# AFE_Channel_4.net
KiCad netlist of a schematic drawn in Altium Designer
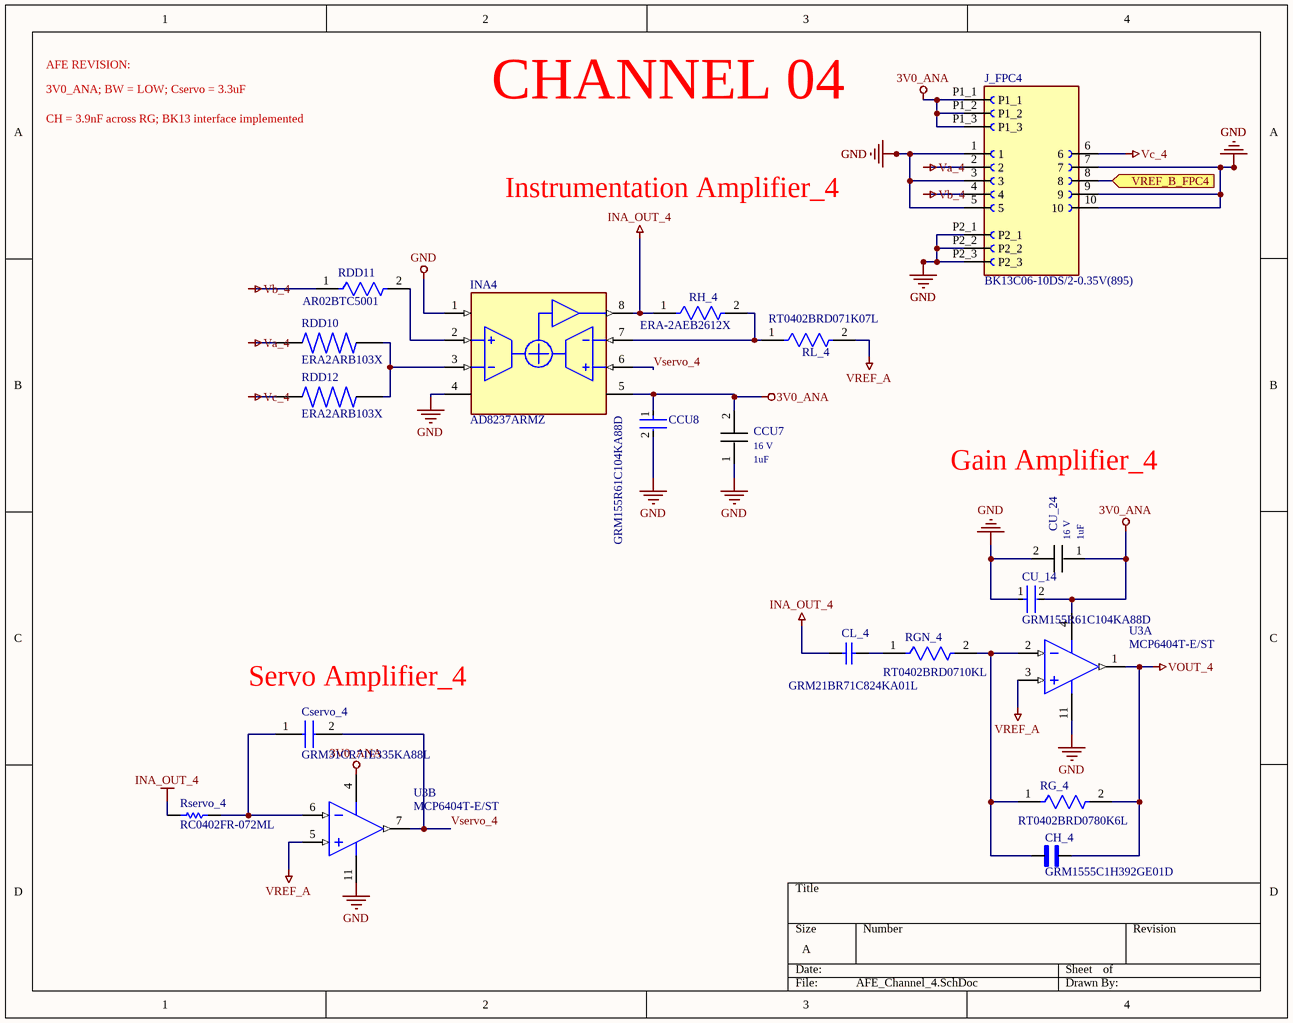
[diagram p0: AFE_Channel_4.SchDoc]

(export (version "E")
  (design (tool "Eeschema 10.0.6"))
  (components
    (comp (ref "CCU7")
      (value "MURATA_GRM155C71C105KE11D")
      (footprint "MURATA_GRM155C71C105KE11D_0:*MURATA_GRM155C71C105KE11D_0")
      (description "Murata GRM155C71C105KE11D: 1 uF 16 V X7S +/-10%, 0402/1005 metric")
      (fields (field (name "MF") "Murata") (field (name "MP") "GRM155C71C105KE11D"))
      (libsource (lib "EMG_Controlled_R5") (part "EMG_R5_CCU7"))
    )
    (comp (ref "CCU8")
      (value "GRM155R61C104KA88D")
      (footprint "96DF66F8-B997-472F-A885-42BCAAE661B2_FP-GRM155-0_05-IPC_C:FP-GRM155-0_05-IPC_C")
      (description "CAP CER 0.1UF 16V X5R 0402")
      (fields (field (name "VOLTAGE") "16V") (field (name "TOLERANCE") "10%"))
      (libsource (lib "EMG_Controlled_R5") (part "EMG_R5_CCU8"))
    )
    (comp (ref "CH_4")
      (value "GRM1555C1H392GE01D")
      (footprint "GRM1555C1H392GE01D_0:CAPC1005X55N")
      (description "SMD capacitor C0G(EIA) with capacitance 3900pF Tol.2%. Rated voltage 50Vdc 125C")
      (fields (field (name "MF") "Murata Electronics"))
      (libsource (lib "EMG_Controlled_R5") (part "EMG_R5_CH_4"))
    )
    (comp (ref "CL_4")
      (value "GRM21BR71C824KA01L")
      (footprint "987105EF-01FA-4198-A59F-44D3B68BB40E_CAPC2013X135X45ML10T25:CAPC2013X135X45ML10T25")
      (fields (field (name "MANUFACTURER") "Murata"))
      (libsource (lib "EMG_Controlled_R5") (part "EMG_R5_CL_4"))
    )
    (comp (ref "Cservo_4")
      (value "GRM31CR71E335KA88L")
      (footprint "SamacSys:GRM31x")
      (description "Capacitor")
      (fields
        (field (name "MOUSER PART NUMBER") "81-GRM31CR71E335KA8L")
        (field (name "MANUFACTURER") "Murata")
      )
      (libsource (lib "EMG_Controlled_R5") (part "EMG_R5_Cservo_4"))
    )
    (comp (ref "CU_14")
      (value "GRM155R61C104KA88D")
      (footprint "96DF66F8-B997-472F-A885-42BCAAE661B2_FP-GRM155-0_05-IPC_C:FP-GRM155-0_05-IPC_C")
      (description "CAP CER 0.1UF 16V X5R 0402")
      (fields (field (name "VOLTAGE") "16V") (field (name "TOLERANCE") "10%"))
      (libsource (lib "EMG_Controlled_R5") (part "EMG_R5_CU_14"))
    )
    (comp (ref "CU_24")
      (value "MURATA_GRM155C71C105KE11D")
      (footprint "MURATA_GRM155C71C105KE11D_0:*MURATA_GRM155C71C105KE11D_0")
      (description "Murata GRM155C71C105KE11D: 1 uF 16 V X7S +/-10%, 0402/1005 metric")
      (fields (field (name "MF") "Murata") (field (name "MP") "GRM155C71C105KE11D"))
      (libsource (lib "EMG_Controlled_R5") (part "EMG_R5_CU_24"))
    )
    (comp (ref "INA4")
      (value "AD8237ARMZ")
      (footprint "EMG_AD8237_R3:EMG_AD8237_R3_MSOP8")
      (description "Micropower, Zero Drift, True Rail-to-Rail Instrumentation Amplifier")
      (fields (field (name "MF") "Analog Devices"))
      (libsource (lib "EMG_Controlled_R5") (part "EMG_R5_INA4"))
    )
    (comp (ref "J_FPC4")
      (value "BK13C06-10DS/2-0.35V(895)")
      (footprint "BK13C06-10DS_2-0.35V_895__0:HIROSE_BK13C06-10DS/2-0.35V(895)")
      (description "10 Position Connector Receptacle, Center Strip Contacts Surface Mount Gold")
      (fields (field (name "MF") "Hirose Electric Co Ltd"))
      (libsource (lib "EMG_Controlled_R5") (part "EMG_R5_J_FPC4"))
    )
    (comp (ref "RDD10")
      (value "ERA2ARB103X")
      (footprint "ERA2ARB103X_0:RES_ERA2ARB103X")
      (libsource (lib "EMG_Controlled_R5") (part "EMG_R5_RDD10"))
    )
    (comp (ref "RDD11")
      (value "AR02BTC5001")
      (footprint "7D606042-220B-45EE-95DD-CA1A974E4C0D_FP-AC0402-MFG:FP-AC0402-MFG")
      (description "-55℃~+155℃ 50V 5kΩ 63mW Thin Film Resistor ±0.1% ±25ppm/℃ 0402 Chip Resistor - Surface Mount ROH")
      (fields
        (field (name "MANUFACTURER") "Viking Tech")
        (field (name "OCTOPART") "https://octopart.com/datasheet/viking-tech/AR02BTC5001")
      )
      (libsource (lib "EMG_Controlled_R5") (part "EMG_R5_RDD11"))
    )
    (comp (ref "RDD12")
      (value "ERA2ARB103X")
      (footprint "ERA2ARB103X_0:RES_ERA2ARB103X")
      (libsource (lib "EMG_Controlled_R5") (part "EMG_R5_RDD12"))
    )
    (comp (ref "RGN_4")
      (value "RT0402BRD0710KL")
      (footprint "B876F212-A29A-4983-9BB8-539D1BA2EBA1_FP-RT0402-MFG:FP-RT0402-MFG")
      (description "RES 10.0K OHM 1/16W .1% SMD 0402")
      (fields
        (field (name "MANUFACTURER") "Yageo")
        (field (name "OCTOPART") "https://octopart.com/rt0402brd0710kl-yageo-1181432")
      )
      (libsource (lib "EMG_Controlled_R5") (part "EMG_R5_RGN_4"))
    )
    (comp (ref "RG_4")
      (value "RT0402BRD0780K6L")
      (footprint "B876F212-A29A-4983-9BB8-539D1BA2EBA1_FP-RT0402-MFG:FP-RT0402-MFG")
      (description "RES SMD 80.6KOHM 0.1% 1/16W 0402")
      (fields
        (field (name "MANUFACTURER") "Yageo")
        (field (name "OCTOPART") "https://octopart.com/rt0402brd0780k6l-yageo-1468076")
      )
      (libsource (lib "EMG_Controlled_R5") (part "EMG_R5_RG_4"))
    )
    (comp (ref "RH_4")
      (value "ERA-2AEB2612X")
      (footprint "1CBBEC27-AD79-48E8-A701-2E235EA9F8F2_FP-AC0402-IPC_A:FP-AC0402-IPC_A")
      (description "RES 26.1kΩ ±0.1% 0.063W 0402")
      (fields (field (name "TOLERANCE") "0.1%") (field (name "MANUFACTURER") "PANASONIC"))
      (libsource (lib "EMG_Controlled_R5") (part "EMG_R5_RH_4"))
    )
    (comp (ref "RL_4")
      (value "RT0402BRD071K07L")
      (footprint "B876F212-A29A-4983-9BB8-539D1BA2EBA1_FP-RT0402-MFG:FP-RT0402-MFG")
      (description "RES SMD 1.07K OHM 0.1% 1/16W")
      (fields
        (field (name "OCTOPART") "https://octopart.com/rt0402brd071k07l-yageo-1400807")
        (field (name "MANUFACTURER") "Yageo")
      )
      (libsource (lib "EMG_Controlled_R5") (part "EMG_R5_RL_4"))
    )
    (comp (ref "Rservo_4")
      (value "RC0402FR-072ML")
      (footprint "3EB15388-1759-44FF-BAE1-1F0823F3E8F1_RESC1005X40X25NL05T10:RESC1005X40X25NL05T10")
      (fields (field (name "MANUFACTURER") "Yageo / Phycomp"))
      (libsource (lib "EMG_Controlled_R5") (part "EMG_R5_Rservo_4"))
    )
    (comp (ref "U3")
      (value "MCP6404T-E/ST")
      (footprint "CEF93338-31F0-4C64-85B6-F650E0BB75E3_TSSOP-ST14_N:TSSOP-ST14_N")
      (description "None")
      (libsource (lib "EMG_Controlled_R5") (part "EMG_R5_U3"))
    )
  )
  (nets
    (net (code "1") (name "/VREF_B_FPC4") (class "Default")
      (node (ref "J_FPC4") (pin "8") (pinfunction "8_8") (pintype "passive"))
    )
    (net (code "2") (name "/Vservo_4") (class "Default")
      (node (ref "Cservo_4") (pin "2") (pinfunction "2_2") (pintype "passive"))
      (node (ref "INA4") (pin "6") (pinfunction "REF_6") (pintype "input"))
      (node (ref "U3") (pin "7") (pinfunction "VOUTB_7") (pintype "output"))
    )
    (net (code "3") (name "3V0_ANA") (class "Default")
      (node (ref "CCU7") (pin "2") (pinfunction "2_2") (pintype "passive"))
      (node (ref "CCU8") (pin "1") (pinfunction "1_1") (pintype "passive"))
      (node (ref "CU_14") (pin "2") (pinfunction "2_2") (pintype "passive"))
      (node (ref "CU_24") (pin "1") (pinfunction "1_1") (pintype "passive"))
      (node (ref "INA4") (pin "5") (pinfunction "+VS_5") (pintype "power_in"))
      (node (ref "J_FPC4") (pin "P1_1") (pinfunction "P1_1_P1_1") (pintype "power_in"))
      (node (ref "J_FPC4") (pin "P1_2") (pinfunction "P1_2_P1_2") (pintype "power_in"))
      (node (ref "J_FPC4") (pin "P1_3") (pinfunction "P1_3_P1_3") (pintype "power_in"))
      (node (ref "U3") (pin "4") (pinfunction "VDD_4") (pintype "power_in"))
    )
    (net (code "4") (name "GND") (class "Default")
      (node (ref "CCU7") (pin "1") (pinfunction "1_1") (pintype "passive"))
      (node (ref "CCU8") (pin "2") (pinfunction "2_2") (pintype "passive"))
      (node (ref "CU_14") (pin "1") (pinfunction "1_1") (pintype "passive"))
      (node (ref "CU_24") (pin "2") (pinfunction "2_2") (pintype "passive"))
      (node (ref "INA4") (pin "1") (pinfunction "BW_1") (pintype "input"))
      (node (ref "INA4") (pin "4") (pinfunction "-VS_4") (pintype "power_in"))
      (node (ref "J_FPC4") (pin "1") (pinfunction "1_1") (pintype "passive"))
      (node (ref "J_FPC4") (pin "10") (pinfunction "10_10") (pintype "passive"))
      (node (ref "J_FPC4") (pin "3") (pinfunction "3_3") (pintype "passive"))
      (node (ref "J_FPC4") (pin "5") (pinfunction "5_5") (pintype "passive"))
      (node (ref "J_FPC4") (pin "7") (pinfunction "7_7") (pintype "passive"))
      (node (ref "J_FPC4") (pin "9") (pinfunction "9_9") (pintype "passive"))
      (node (ref "J_FPC4") (pin "P2_1") (pinfunction "P2_1_P2_1") (pintype "power_in"))
      (node (ref "J_FPC4") (pin "P2_2") (pinfunction "P2_2_P2_2") (pintype "power_in"))
      (node (ref "J_FPC4") (pin "P2_3") (pinfunction "P2_3_P2_3") (pintype "power_in"))
      (node (ref "U3") (pin "11") (pinfunction "VSS_11") (pintype "power_in"))
    )
    (net (code "5") (name "INA_OUT_4") (class "Default")
      (node (ref "CL_4") (pin "2") (pinfunction "2_2") (pintype "passive"))
      (node (ref "INA4") (pin "8") (pinfunction "VOUT_8") (pintype "output"))
      (node (ref "RH_4") (pin "1") (pinfunction "1_1") (pintype "passive"))
      (node (ref "Rservo_4") (pin "2") (pinfunction "2_2") (pintype "passive"))
    )
    (net (code "6") (name "Net-(CL_4-Pad1)") (class "Default")
      (node (ref "CL_4") (pin "1") (pinfunction "1_1") (pintype "passive"))
      (node (ref "RGN_4") (pin "1") (pinfunction "1_1") (pintype "passive"))
    )
    (net (code "7") (name "Net-(INA4-+IN)") (class "Default")
      (node (ref "INA4") (pin "2") (pinfunction "+IN_2") (pintype "input"))
      (node (ref "RDD11") (pin "2") (pinfunction "2_2") (pintype "passive"))
    )
    (net (code "8") (name "Net-(INA4--IN)") (class "Default")
      (node (ref "INA4") (pin "3") (pinfunction "-IN_3") (pintype "input"))
      (node (ref "RDD10") (pin "2") (pinfunction "2_2") (pintype "passive"))
      (node (ref "RDD12") (pin "2") (pinfunction "2_2") (pintype "passive"))
    )
    (net (code "9") (name "Net-(INA4-FB)") (class "Default")
      (node (ref "INA4") (pin "7") (pinfunction "FB_7") (pintype "input"))
      (node (ref "RH_4") (pin "2") (pinfunction "2_2") (pintype "passive"))
      (node (ref "RL_4") (pin "1") (pinfunction "1_1") (pintype "passive"))
    )
    (net (code "10") (name "Net-(U3A-VINA-)") (class "Default")
      (node (ref "CH_4") (pin "2") (pinfunction "2_2") (pintype "passive"))
      (node (ref "RGN_4") (pin "2") (pinfunction "2_2") (pintype "passive"))
      (node (ref "RG_4") (pin "1") (pinfunction "1_1") (pintype "passive"))
      (node (ref "U3") (pin "2") (pinfunction "VINA-_2") (pintype "input"))
    )
    (net (code "11") (name "Net-(U3B-VINB-)") (class "Default")
      (node (ref "Cservo_4") (pin "1") (pinfunction "1_1") (pintype "passive"))
      (node (ref "Rservo_4") (pin "1") (pinfunction "1_1") (pintype "passive"))
      (node (ref "U3") (pin "6") (pinfunction "VINB-_6") (pintype "input"))
    )
    (net (code "12") (name "VOUT_4") (class "Default")
      (node (ref "CH_4") (pin "1") (pinfunction "1_1") (pintype "passive"))
      (node (ref "RG_4") (pin "2") (pinfunction "2_2") (pintype "passive"))
      (node (ref "U3") (pin "1") (pinfunction "VOUTA_1") (pintype "output"))
    )
    (net (code "13") (name "VREF_A") (class "Default")
      (node (ref "RL_4") (pin "2") (pinfunction "2_2") (pintype "passive"))
      (node (ref "U3") (pin "3") (pinfunction "VINA+_3") (pintype "input"))
      (node (ref "U3") (pin "5") (pinfunction "VINB+_5") (pintype "input"))
    )
    (net (code "14") (name "Va_4") (class "Default")
      (node (ref "J_FPC4") (pin "2") (pinfunction "2_2") (pintype "passive"))
      (node (ref "RDD10") (pin "1") (pinfunction "1_1") (pintype "passive"))
    )
    (net (code "15") (name "Vb_4") (class "Default")
      (node (ref "J_FPC4") (pin "4") (pinfunction "4_4") (pintype "passive"))
      (node (ref "RDD11") (pin "1") (pinfunction "1_1") (pintype "passive"))
    )
    (net (code "16") (name "Vc_4") (class "Default")
      (node (ref "J_FPC4") (pin "6") (pinfunction "6_6") (pintype "passive"))
      (node (ref "RDD12") (pin "1") (pinfunction "1_1") (pintype "passive"))
    )
  )
)
